# SpaceInvaders-v20.net
KiCad netlist of a schematic drawn in EAGLE
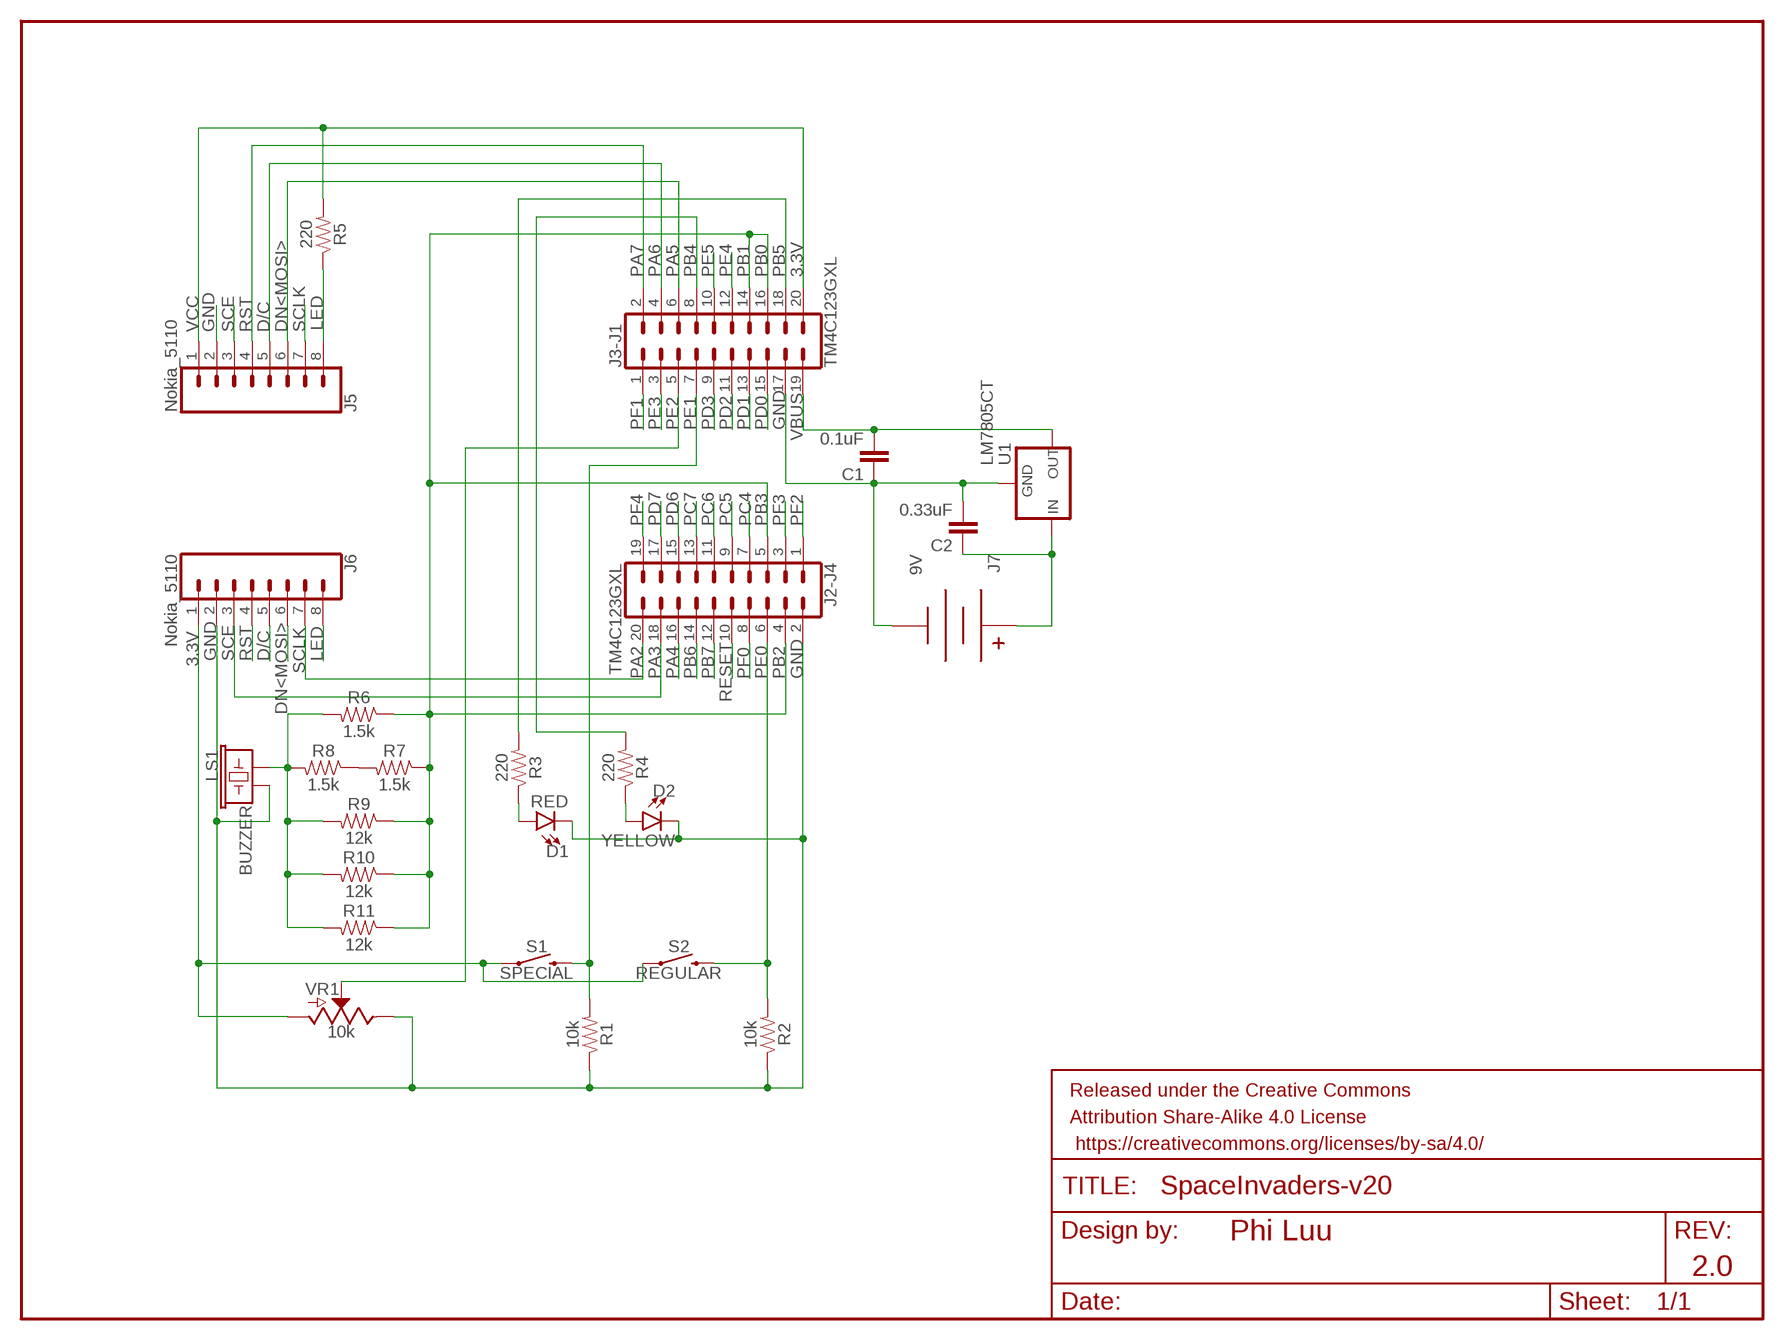
[diagram p0: schematic, sheet 1]

(export (version "E")
  (design (tool "Eeschema 10.0.6"))
  (components
    (comp (ref "C1")
      (value "0.1uF")
      (footprint "eagle-import:CAP-PTH-SMALL-KIT")
      (libsource (lib "eagle-import") (part "0.1UF-KIT-EZ-50V-20%"))
    )
    (comp (ref "C2")
      (value "0.33uF")
      (footprint "eagle-import:CAP-PTH-SMALL-KIT")
      (libsource (lib "eagle-import") (part "0.1UF-KIT-EZ-50V-20%"))
    )
    (comp (ref "D1")
      (value "RED")
      (footprint "eagle-import:LED_5MM")
      (libsource (lib "eagle-import") (part "LED5MM"))
    )
    (comp (ref "D2")
      (value "YELLOW")
      (footprint "eagle-import:LED_5MM")
      (libsource (lib "eagle-import") (part "LED5MM"))
    )
    (comp (ref "FRAME1")
      (value "FRAME-LETTER")
      (footprint "eagle-import:CREATIVE_COMMONS")
      (libsource (lib "eagle-import") (part "FRAME-LETTER"))
    )
    (comp (ref "J2-J4")
      (value "TM4C123GXL")
      (footprint "eagle-import:2X10")
      (libsource (lib "eagle-import") (part "CONN_10X2"))
    )
    (comp (ref "J3-J1")
      (value "TM4C123GXL")
      (footprint "eagle-import:2X10")
      (libsource (lib "eagle-import") (part "CONN_10X2"))
    )
    (comp (ref "J5")
      (value "Nokia_5110")
      (footprint "eagle-import:1X08")
      (libsource (lib "eagle-import") (part "CONN_08{dblquote}"))
    )
    (comp (ref "J6")
      (value "Nokia_5110")
      (footprint "eagle-import:1X08")
      (libsource (lib "eagle-import") (part "CONN_08{dblquote}"))
    )
    (comp (ref "J7")
      (value "9V")
      (footprint "eagle-import:BC9VPC")
      (libsource (lib "eagle-import") (part "BC9VPC"))
    )
    (comp (ref "LS1")
      (value "BUZZER")
      (footprint "eagle-import:BUZZER-12MM")
      (libsource (lib "eagle-import") (part "BUZZER-PTH"))
    )
    (comp (ref "R1")
      (value "10k")
      (footprint "eagle-import:AXIAL-0.3")
      (libsource (lib "eagle-import") (part "10KOHM-HORIZ-1/4W-5%"))
    )
    (comp (ref "R2")
      (value "10k")
      (footprint "eagle-import:AXIAL-0.3")
      (libsource (lib "eagle-import") (part "10KOHM-HORIZ-1/4W-5%"))
    )
    (comp (ref "R3")
      (value "220")
      (footprint "eagle-import:AXIAL-0.3")
      (libsource (lib "eagle-import") (part "1KOHM-HORIZ-1/4W-5%"))
    )
    (comp (ref "R4")
      (value "220")
      (footprint "eagle-import:AXIAL-0.3")
      (libsource (lib "eagle-import") (part "1KOHM-HORIZ-1/4W-5%"))
    )
    (comp (ref "R5")
      (value "220")
      (footprint "eagle-import:AXIAL-0.3")
      (libsource (lib "eagle-import") (part "1KOHM-HORIZ-1/4W-5%"))
    )
    (comp (ref "R6")
      (value "1.5k")
      (footprint "eagle-import:AXIAL-0.3")
      (libsource (lib "eagle-import") (part "1KOHM-HORIZ-1/4W-5%"))
    )
    (comp (ref "R7")
      (value "1.5k")
      (footprint "eagle-import:AXIAL-0.3")
      (libsource (lib "eagle-import") (part "1KOHM-HORIZ-1/4W-5%"))
    )
    (comp (ref "R8")
      (value "1.5k")
      (footprint "eagle-import:AXIAL-0.3")
      (libsource (lib "eagle-import") (part "1KOHM-HORIZ-1/4W-5%"))
    )
    (comp (ref "R9")
      (value "12k")
      (footprint "eagle-import:AXIAL-0.3")
      (libsource (lib "eagle-import") (part "1KOHM-HORIZ-1/4W-5%"))
    )
    (comp (ref "R10")
      (value "12k")
      (footprint "eagle-import:AXIAL-0.3")
      (libsource (lib "eagle-import") (part "1KOHM-HORIZ-1/4W-5%"))
    )
    (comp (ref "R11")
      (value "12k")
      (footprint "eagle-import:AXIAL-0.3")
      (libsource (lib "eagle-import") (part "1KOHM-HORIZ-1/4W-5%"))
    )
    (comp (ref "S1")
      (value "SPECIAL")
      (footprint "eagle-import:TACTILE_SWITCH_PTH_6.0MM")
      (libsource (lib "eagle-import") (part "MOMENTARY-SWITCH-SPST-PTH-6.0MM"))
    )
    (comp (ref "S2")
      (value "REGULAR")
      (footprint "eagle-import:TACTILE_SWITCH_PTH_6.0MM")
      (libsource (lib "eagle-import") (part "MOMENTARY-SWITCH-SPST-PTH-6.0MM"))
    )
    (comp (ref "U1")
      (value "LM7805CT")
      (footprint "eagle-import:TO-220-ALT")
      (libsource (lib "eagle-import") (part "V_REG_78XX-TO-220"))
    )
    (comp (ref "VR1")
      (value "10k")
      (footprint "eagle-import:SLIDER-MEDIUM")
      (libsource (lib "eagle-import") (part "POTENTIOMETER_SLIDE-30MM-1/10W-20%"))
    )
  )
  (nets
    (net (code "1") (name "/3.3V") (class "Default")
      (node (ref "J3-J1") (pin "20") (pinfunction "20_20") (pintype "passive"))
      (node (ref "J5") (pin "1") (pinfunction "1_1") (pintype "passive"))
      (node (ref "J6") (pin "1") (pinfunction "1_1") (pintype "passive"))
      (node (ref "R5") (pin "P$2") (pinfunction "2_P$2") (pintype "passive"))
      (node (ref "S1") (pin "1") (pinfunction "1_1") (pintype "passive"))
      (node (ref "S2") (pin "1") (pinfunction "1_1") (pintype "passive"))
      (node (ref "VR1") (pin "BOTTOM") (pinfunction "A_BOTTOM") (pintype "passive"))
    )
    (net (code "2") (name "/DN<MOSI>") (class "Default")
      (node (ref "J6") (pin "6") (pinfunction "6_6") (pintype "passive"))
    )
    (net (code "3") (name "/D{slash}C") (class "Default")
      (node (ref "J6") (pin "5") (pinfunction "5_5") (pintype "passive"))
    )
    (net (code "4") (name "/GND") (class "Default")
      (node (ref "C1") (pin "1") (pinfunction "1_1") (pintype "passive"))
      (node (ref "C2") (pin "2") (pinfunction "2_2") (pintype "passive"))
      (node (ref "D1") (pin "K") (pinfunction "C_K") (pintype "passive"))
      (node (ref "D2") (pin "K") (pinfunction "C_K") (pintype "passive"))
      (node (ref "J2-J4") (pin "2") (pinfunction "2_2") (pintype "passive"))
      (node (ref "J3-J1") (pin "17") (pinfunction "17_17") (pintype "passive"))
      (node (ref "J5") (pin "2") (pinfunction "2_2") (pintype "passive"))
      (node (ref "J6") (pin "2") (pinfunction "2_2") (pintype "passive"))
      (node (ref "J7") (pin "V-") (pinfunction "V-_V-") (pintype "bidirectional"))
      (node (ref "LS1") (pin "-") (pinfunction "2_-") (pintype "passive"))
      (node (ref "R1") (pin "P$1") (pinfunction "1_P$1") (pintype "passive"))
      (node (ref "R2") (pin "P$1") (pinfunction "1_P$1") (pintype "passive"))
      (node (ref "U1") (pin "GND") (pinfunction "GND_GND") (pintype "input"))
      (node (ref "VR1") (pin "TOP") (pinfunction "E_TOP") (pintype "passive"))
    )
    (net (code "5") (name "/LED") (class "Default")
      (node (ref "J5") (pin "8") (pinfunction "8_8") (pintype "passive"))
      (node (ref "J6") (pin "8") (pinfunction "8_8") (pintype "passive"))
      (node (ref "R5") (pin "P$1") (pinfunction "1_P$1") (pintype "passive"))
    )
    (net (code "6") (name "/PA2") (class "Default")
      (node (ref "J2-J4") (pin "20") (pinfunction "20_20") (pintype "passive"))
      (node (ref "J6") (pin "7") (pinfunction "7_7") (pintype "passive"))
    )
    (net (code "7") (name "/PA3") (class "Default")
      (node (ref "J2-J4") (pin "18") (pinfunction "18_18") (pintype "passive"))
      (node (ref "J6") (pin "3") (pinfunction "3_3") (pintype "passive"))
    )
    (net (code "8") (name "/PA4") (class "Default")
      (node (ref "J2-J4") (pin "16") (pinfunction "16_16") (pintype "passive"))
    )
    (net (code "9") (name "/PA5") (class "Default")
      (node (ref "J3-J1") (pin "6") (pinfunction "6_6") (pintype "passive"))
      (node (ref "J5") (pin "6") (pinfunction "6_6") (pintype "passive"))
    )
    (net (code "10") (name "/PA6") (class "Default")
      (node (ref "J3-J1") (pin "4") (pinfunction "4_4") (pintype "passive"))
      (node (ref "J5") (pin "5") (pinfunction "5_5") (pintype "passive"))
    )
    (net (code "11") (name "/PA7") (class "Default")
      (node (ref "J3-J1") (pin "2") (pinfunction "2_2") (pintype "passive"))
      (node (ref "J5") (pin "4") (pinfunction "4_4") (pintype "passive"))
    )
    (net (code "12") (name "/PB2") (class "Default")
      (node (ref "J2-J4") (pin "4") (pinfunction "4_4") (pintype "passive"))
      (node (ref "J2-J4") (pin "5") (pinfunction "5_5") (pintype "passive"))
      (node (ref "J3-J1") (pin "14") (pinfunction "14_14") (pintype "passive"))
      (node (ref "J3-J1") (pin "16") (pinfunction "16_16") (pintype "passive"))
      (node (ref "R10") (pin "P$1") (pinfunction "1_P$1") (pintype "passive"))
      (node (ref "R11") (pin "P$1") (pinfunction "1_P$1") (pintype "passive"))
      (node (ref "R6") (pin "P$1") (pinfunction "1_P$1") (pintype "passive"))
      (node (ref "R7") (pin "P$1") (pinfunction "1_P$1") (pintype "passive"))
      (node (ref "R9") (pin "P$1") (pinfunction "1_P$1") (pintype "passive"))
    )
    (net (code "13") (name "/PB4") (class "Default")
      (node (ref "J3-J1") (pin "8") (pinfunction "8_8") (pintype "passive"))
      (node (ref "R4") (pin "P$2") (pinfunction "2_P$2") (pintype "passive"))
    )
    (net (code "14") (name "/PB5") (class "Default")
      (node (ref "J3-J1") (pin "18") (pinfunction "18_18") (pintype "passive"))
      (node (ref "R3") (pin "P$2") (pinfunction "2_P$2") (pintype "passive"))
    )
    (net (code "15") (name "/PB6") (class "Default")
      (node (ref "J2-J4") (pin "14") (pinfunction "14_14") (pintype "passive"))
    )
    (net (code "16") (name "/PB7") (class "Default")
      (node (ref "J2-J4") (pin "12") (pinfunction "12_12") (pintype "passive"))
    )
    (net (code "17") (name "/PC4") (class "Default")
      (node (ref "J2-J4") (pin "7") (pinfunction "7_7") (pintype "passive"))
    )
    (net (code "18") (name "/PC5") (class "Default")
      (node (ref "J2-J4") (pin "9") (pinfunction "9_9") (pintype "passive"))
    )
    (net (code "19") (name "/PC6") (class "Default")
      (node (ref "J2-J4") (pin "11") (pinfunction "11_11") (pintype "passive"))
    )
    (net (code "20") (name "/PC7") (class "Default")
      (node (ref "J2-J4") (pin "13") (pinfunction "13_13") (pintype "passive"))
    )
    (net (code "21") (name "/PD0") (class "Default")
      (node (ref "J3-J1") (pin "15") (pinfunction "15_15") (pintype "passive"))
    )
    (net (code "22") (name "/PD1") (class "Default")
      (node (ref "J3-J1") (pin "13") (pinfunction "13_13") (pintype "passive"))
    )
    (net (code "23") (name "/PD2") (class "Default")
      (node (ref "J3-J1") (pin "11") (pinfunction "11_11") (pintype "passive"))
    )
    (net (code "24") (name "/PD3") (class "Default")
      (node (ref "J3-J1") (pin "9") (pinfunction "9_9") (pintype "passive"))
    )
    (net (code "25") (name "/PD6") (class "Default")
      (node (ref "J2-J4") (pin "15") (pinfunction "15_15") (pintype "passive"))
    )
    (net (code "26") (name "/PD7") (class "Default")
      (node (ref "J2-J4") (pin "17") (pinfunction "17_17") (pintype "passive"))
    )
    (net (code "27") (name "/PE0") (class "Default")
      (node (ref "J2-J4") (pin "6") (pinfunction "6_6") (pintype "passive"))
      (node (ref "R2") (pin "P$2") (pinfunction "2_P$2") (pintype "passive"))
      (node (ref "S2") (pin "3") (pinfunction "2_3") (pintype "passive"))
    )
    (net (code "28") (name "/PE1") (class "Default")
      (node (ref "J3-J1") (pin "7") (pinfunction "7_7") (pintype "passive"))
      (node (ref "R1") (pin "P$2") (pinfunction "2_P$2") (pintype "passive"))
      (node (ref "S1") (pin "3") (pinfunction "2_3") (pintype "passive"))
    )
    (net (code "29") (name "/PE2") (class "Default")
      (node (ref "J3-J1") (pin "5") (pinfunction "5_5") (pintype "passive"))
      (node (ref "VR1") (pin "WIPER") (pinfunction "S_WIPER") (pintype "passive"))
    )
    (net (code "30") (name "/PE3") (class "Default")
      (node (ref "J3-J1") (pin "3") (pinfunction "3_3") (pintype "passive"))
    )
    (net (code "31") (name "/PE4") (class "Default")
      (node (ref "J3-J1") (pin "12") (pinfunction "12_12") (pintype "passive"))
    )
    (net (code "32") (name "/PE5") (class "Default")
      (node (ref "J3-J1") (pin "10") (pinfunction "10_10") (pintype "passive"))
    )
    (net (code "33") (name "/PF0") (class "Default")
      (node (ref "J2-J4") (pin "8") (pinfunction "8_8") (pintype "passive"))
    )
    (net (code "34") (name "/PF1") (class "Default")
      (node (ref "J3-J1") (pin "1") (pinfunction "1_1") (pintype "passive"))
    )
    (net (code "35") (name "/PF2") (class "Default")
      (node (ref "J2-J4") (pin "1") (pinfunction "1_1") (pintype "passive"))
    )
    (net (code "36") (name "/PF3") (class "Default")
      (node (ref "J2-J4") (pin "3") (pinfunction "3_3") (pintype "passive"))
    )
    (net (code "37") (name "/PF4") (class "Default")
      (node (ref "J2-J4") (pin "19") (pinfunction "19_19") (pintype "passive"))
    )
    (net (code "38") (name "/RESET") (class "Default")
      (node (ref "J2-J4") (pin "10") (pinfunction "10_10") (pintype "passive"))
    )
    (net (code "39") (name "/RST") (class "Default")
      (node (ref "J6") (pin "4") (pinfunction "4_4") (pintype "passive"))
    )
    (net (code "40") (name "/SCE") (class "Default")
      (node (ref "J5") (pin "3") (pinfunction "3_3") (pintype "passive"))
    )
    (net (code "41") (name "/SCLK") (class "Default")
      (node (ref "J5") (pin "7") (pinfunction "7_7") (pintype "passive"))
    )
    (net (code "42") (name "/VBUS") (class "Default")
      (node (ref "C1") (pin "2") (pinfunction "2_2") (pintype "passive"))
      (node (ref "J3-J1") (pin "19") (pinfunction "19_19") (pintype "passive"))
      (node (ref "U1") (pin "OUT") (pinfunction "OUT_OUT") (pintype "passive"))
    )
    (net (code "43") (name "Net-(C2-Pad1)") (class "Default")
      (node (ref "C2") (pin "1") (pinfunction "1_1") (pintype "passive"))
      (node (ref "J7") (pin "V+") (pinfunction "V+_V+") (pintype "bidirectional"))
      (node (ref "U1") (pin "IN") (pinfunction "IN_IN") (pintype "input"))
    )
    (net (code "44") (name "Net-(LS1-1)") (class "Default")
      (node (ref "LS1") (pin "+") (pinfunction "1_+") (pintype "passive"))
      (node (ref "R10") (pin "P$2") (pinfunction "2_P$2") (pintype "passive"))
      (node (ref "R11") (pin "P$2") (pinfunction "2_P$2") (pintype "passive"))
      (node (ref "R6") (pin "P$2") (pinfunction "2_P$2") (pintype "passive"))
      (node (ref "R8") (pin "P$2") (pinfunction "2_P$2") (pintype "passive"))
      (node (ref "R9") (pin "P$2") (pinfunction "2_P$2") (pintype "passive"))
    )
    (net (code "45") (name "Net-(R3-1)") (class "Default")
      (node (ref "D1") (pin "A") (pinfunction "A_A") (pintype "passive"))
      (node (ref "R3") (pin "P$1") (pinfunction "1_P$1") (pintype "passive"))
    )
    (net (code "46") (name "Net-(R4-1)") (class "Default")
      (node (ref "D2") (pin "A") (pinfunction "A_A") (pintype "passive"))
      (node (ref "R4") (pin "P$1") (pinfunction "1_P$1") (pintype "passive"))
    )
    (net (code "47") (name "Net-(R7-2)") (class "Default")
      (node (ref "R7") (pin "P$2") (pinfunction "2_P$2") (pintype "passive"))
      (node (ref "R8") (pin "P$1") (pinfunction "1_P$1") (pintype "passive"))
    )
  )
)
